# encoder_isolator.net
KiCad netlist of a schematic drawn in EAGLE
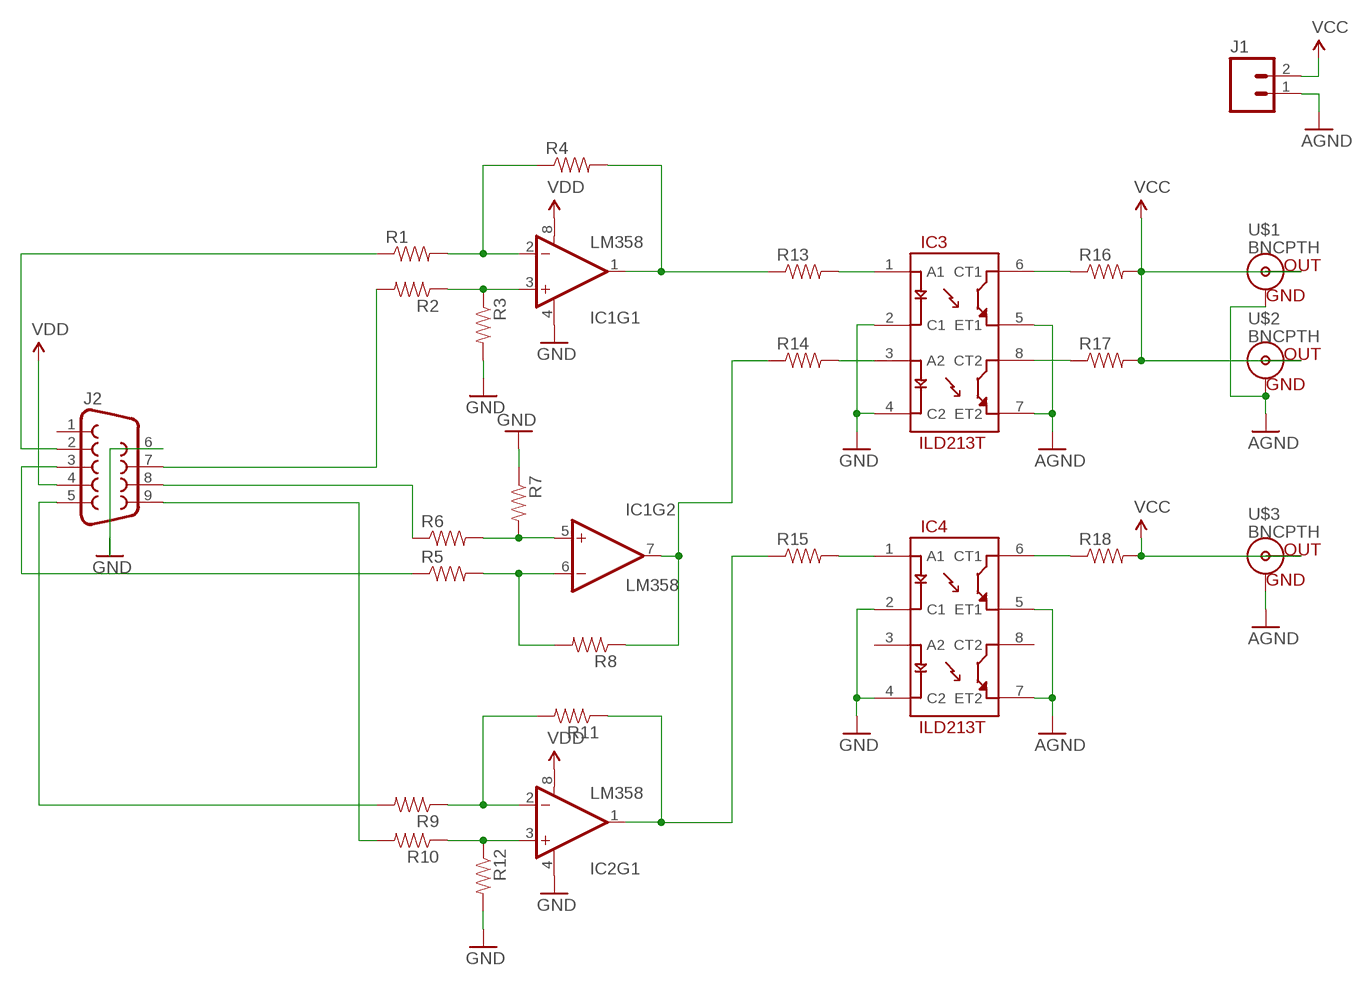
[diagram p0: schematic, sheet 1]

(export (version "E")
  (design (tool "Eeschema 10.0.6"))
  (components
    (comp (ref "IC1")
      (value "LM358")
      (footprint "eagle-import:DIP08")
      (libsource (lib "eagle-import") (part "LM358"))
    )
    (comp (ref "IC2")
      (value "LM358")
      (footprint "eagle-import:DIP08")
      (libsource (lib "eagle-import") (part "LM358"))
    )
    (comp (ref "IC3")
      (value "ILD213T")
      (footprint "eagle-import:SO08")
      (libsource (lib "eagle-import") (part "ILD213T"))
    )
    (comp (ref "IC4")
      (value "ILD213T")
      (footprint "eagle-import:SO08")
      (libsource (lib "eagle-import") (part "ILD213T"))
    )
    (comp (ref "J1")
      (value "M02POLAR")
      (footprint "eagle-import:MOLEX-1X2")
      (libsource (lib "eagle-import") (part "M02POLAR"))
    )
    (comp (ref "J2")
      (value "DB9FEMALE")
      (footprint "eagle-import:DB9")
      (libsource (lib "eagle-import") (part "DB9FEMALE"))
    )
    (comp (ref "R1")
      (value "RESISTORPTH-1/4W")
      (footprint "eagle-import:AXIAL-0.4")
      (libsource (lib "eagle-import") (part "RESISTORPTH-1/4W"))
    )
    (comp (ref "R2")
      (value "RESISTORPTH-1/4W")
      (footprint "eagle-import:AXIAL-0.4")
      (libsource (lib "eagle-import") (part "RESISTORPTH-1/4W"))
    )
    (comp (ref "R3")
      (value "RESISTORPTH-1/4W")
      (footprint "eagle-import:AXIAL-0.4")
      (libsource (lib "eagle-import") (part "RESISTORPTH-1/4W"))
    )
    (comp (ref "R4")
      (value "RESISTORPTH-1/4W")
      (footprint "eagle-import:AXIAL-0.4")
      (libsource (lib "eagle-import") (part "RESISTORPTH-1/4W"))
    )
    (comp (ref "R5")
      (value "RESISTORPTH-1/4W")
      (footprint "eagle-import:AXIAL-0.4")
      (libsource (lib "eagle-import") (part "RESISTORPTH-1/4W"))
    )
    (comp (ref "R6")
      (value "RESISTORPTH-1/4W")
      (footprint "eagle-import:AXIAL-0.4")
      (libsource (lib "eagle-import") (part "RESISTORPTH-1/4W"))
    )
    (comp (ref "R7")
      (value "RESISTORPTH-1/4W")
      (footprint "eagle-import:AXIAL-0.4")
      (libsource (lib "eagle-import") (part "RESISTORPTH-1/4W"))
    )
    (comp (ref "R8")
      (value "RESISTORPTH-1/4W")
      (footprint "eagle-import:AXIAL-0.4")
      (libsource (lib "eagle-import") (part "RESISTORPTH-1/4W"))
    )
    (comp (ref "R9")
      (value "RESISTORPTH-1/4W")
      (footprint "eagle-import:AXIAL-0.4")
      (libsource (lib "eagle-import") (part "RESISTORPTH-1/4W"))
    )
    (comp (ref "R10")
      (value "RESISTORPTH-1/4W")
      (footprint "eagle-import:AXIAL-0.4")
      (libsource (lib "eagle-import") (part "RESISTORPTH-1/4W"))
    )
    (comp (ref "R11")
      (value "RESISTORPTH-1/4W")
      (footprint "eagle-import:AXIAL-0.4")
      (libsource (lib "eagle-import") (part "RESISTORPTH-1/4W"))
    )
    (comp (ref "R12")
      (value "RESISTORPTH-1/4W")
      (footprint "eagle-import:AXIAL-0.4")
      (libsource (lib "eagle-import") (part "RESISTORPTH-1/4W"))
    )
    (comp (ref "R13")
      (value "RESISTORPTH-1/4W")
      (footprint "eagle-import:AXIAL-0.4")
      (libsource (lib "eagle-import") (part "RESISTORPTH-1/4W"))
    )
    (comp (ref "R14")
      (value "RESISTORPTH-1/4W")
      (footprint "eagle-import:AXIAL-0.4")
      (libsource (lib "eagle-import") (part "RESISTORPTH-1/4W"))
    )
    (comp (ref "R15")
      (value "RESISTORPTH-1/4W")
      (footprint "eagle-import:AXIAL-0.4")
      (libsource (lib "eagle-import") (part "RESISTORPTH-1/4W"))
    )
    (comp (ref "R16")
      (value "RESISTORPTH-1/4W")
      (footprint "eagle-import:AXIAL-0.4")
      (libsource (lib "eagle-import") (part "RESISTORPTH-1/4W"))
    )
    (comp (ref "R17")
      (value "RESISTORPTH-1/4W")
      (footprint "eagle-import:AXIAL-0.4")
      (libsource (lib "eagle-import") (part "RESISTORPTH-1/4W"))
    )
    (comp (ref "R18")
      (value "RESISTORPTH-1/4W")
      (footprint "eagle-import:AXIAL-0.4")
      (libsource (lib "eagle-import") (part "RESISTORPTH-1/4W"))
    )
    (comp (ref "U$1")
      (value "BNCPTH")
      (footprint "eagle-import:BNC")
      (libsource (lib "eagle-import") (part "BNCPTH"))
    )
    (comp (ref "U$2")
      (value "BNCPTH")
      (footprint "eagle-import:BNC")
      (libsource (lib "eagle-import") (part "BNCPTH"))
    )
    (comp (ref "U$3")
      (value "BNCPTH")
      (footprint "eagle-import:BNC")
      (libsource (lib "eagle-import") (part "BNCPTH"))
    )
  )
  (nets
    (net (code "1") (name "AGND") (class "Default")
      (node (ref "IC3") (pin "5") (pinfunction "ET1_5") (pintype "bidirectional"))
      (node (ref "IC3") (pin "7") (pinfunction "ET2_7") (pintype "bidirectional"))
      (node (ref "IC4") (pin "5") (pinfunction "ET1_5") (pintype "bidirectional"))
      (node (ref "IC4") (pin "7") (pinfunction "ET2_7") (pintype "bidirectional"))
      (node (ref "J1") (pin "1") (pinfunction "1_1") (pintype "passive"))
      (node (ref "U$1") (pin "GND") (pinfunction "GND_GND") (pintype "bidirectional"))
      (node (ref "U$2") (pin "GND") (pinfunction "GND_GND") (pintype "bidirectional"))
      (node (ref "U$3") (pin "GND") (pinfunction "GND_GND") (pintype "bidirectional"))
    )
    (net (code "2") (name "GND") (class "Default")
      (node (ref "IC1") (pin "4") (pinfunction "V-_4") (pintype "power_in"))
      (node (ref "IC2") (pin "4") (pinfunction "V-_4") (pintype "power_in"))
      (node (ref "IC3") (pin "2") (pinfunction "C1_2") (pintype "bidirectional"))
      (node (ref "IC3") (pin "4") (pinfunction "C2_4") (pintype "bidirectional"))
      (node (ref "IC4") (pin "2") (pinfunction "C1_2") (pintype "bidirectional"))
      (node (ref "IC4") (pin "4") (pinfunction "C2_4") (pintype "bidirectional"))
      (node (ref "J2") (pin "6") (pinfunction "6_6") (pintype "passive"))
      (node (ref "R12") (pin "P$2") (pinfunction "2_P$2") (pintype "passive"))
      (node (ref "R3") (pin "P$2") (pinfunction "2_P$2") (pintype "passive"))
      (node (ref "R7") (pin "P$1") (pinfunction "1_P$1") (pintype "passive"))
    )
    (net (code "3") (name "Net-(IC1A-+IN)") (class "Default")
      (node (ref "IC1") (pin "3") (pinfunction "+IN_3") (pintype "input"))
      (node (ref "R2") (pin "P$1") (pinfunction "1_P$1") (pintype "passive"))
      (node (ref "R3") (pin "P$1") (pinfunction "1_P$1") (pintype "passive"))
    )
    (net (code "4") (name "Net-(IC1A--IN)") (class "Default")
      (node (ref "IC1") (pin "2") (pinfunction "-IN_2") (pintype "input"))
      (node (ref "R1") (pin "P$2") (pinfunction "2_P$2") (pintype "passive"))
      (node (ref "R4") (pin "P$1") (pinfunction "1_P$1") (pintype "passive"))
    )
    (net (code "5") (name "Net-(IC1A-OUT)") (class "Default")
      (node (ref "IC1") (pin "1") (pinfunction "OUT_1") (pintype "output"))
      (node (ref "R13") (pin "P$1") (pinfunction "1_P$1") (pintype "passive"))
      (node (ref "R4") (pin "P$2") (pinfunction "2_P$2") (pintype "passive"))
    )
    (net (code "6") (name "Net-(IC1B-+IN)") (class "Default")
      (node (ref "IC1") (pin "5") (pinfunction "+IN_5") (pintype "input"))
      (node (ref "R6") (pin "P$2") (pinfunction "2_P$2") (pintype "passive"))
      (node (ref "R7") (pin "P$2") (pinfunction "2_P$2") (pintype "passive"))
    )
    (net (code "7") (name "Net-(IC1B--IN)") (class "Default")
      (node (ref "IC1") (pin "6") (pinfunction "-IN_6") (pintype "input"))
      (node (ref "R5") (pin "P$2") (pinfunction "2_P$2") (pintype "passive"))
      (node (ref "R8") (pin "P$2") (pinfunction "2_P$2") (pintype "passive"))
    )
    (net (code "8") (name "Net-(IC1B-OUT)") (class "Default")
      (node (ref "IC1") (pin "7") (pinfunction "OUT_7") (pintype "output"))
      (node (ref "R14") (pin "P$1") (pinfunction "1_P$1") (pintype "passive"))
      (node (ref "R8") (pin "P$1") (pinfunction "1_P$1") (pintype "passive"))
    )
    (net (code "9") (name "Net-(IC2A-+IN)") (class "Default")
      (node (ref "IC2") (pin "3") (pinfunction "+IN_3") (pintype "input"))
      (node (ref "R10") (pin "P$1") (pinfunction "1_P$1") (pintype "passive"))
      (node (ref "R12") (pin "P$1") (pinfunction "1_P$1") (pintype "passive"))
    )
    (net (code "10") (name "Net-(IC2A--IN)") (class "Default")
      (node (ref "IC2") (pin "2") (pinfunction "-IN_2") (pintype "input"))
      (node (ref "R11") (pin "P$2") (pinfunction "2_P$2") (pintype "passive"))
      (node (ref "R9") (pin "P$1") (pinfunction "1_P$1") (pintype "passive"))
    )
    (net (code "11") (name "Net-(IC2A-OUT)") (class "Default")
      (node (ref "IC2") (pin "1") (pinfunction "OUT_1") (pintype "output"))
      (node (ref "R11") (pin "P$1") (pinfunction "1_P$1") (pintype "passive"))
      (node (ref "R15") (pin "P$1") (pinfunction "1_P$1") (pintype "passive"))
    )
    (net (code "12") (name "Net-(IC3-A1)") (class "Default")
      (node (ref "IC3") (pin "1") (pinfunction "A1_1") (pintype "bidirectional"))
      (node (ref "R13") (pin "P$2") (pinfunction "2_P$2") (pintype "passive"))
    )
    (net (code "13") (name "Net-(IC3-A2)") (class "Default")
      (node (ref "IC3") (pin "3") (pinfunction "A2_3") (pintype "bidirectional"))
      (node (ref "R14") (pin "P$2") (pinfunction "2_P$2") (pintype "passive"))
    )
    (net (code "14") (name "Net-(IC3-CT1)") (class "Default")
      (node (ref "IC3") (pin "6") (pinfunction "CT1_6") (pintype "bidirectional"))
      (node (ref "R16") (pin "P$1") (pinfunction "1_P$1") (pintype "passive"))
    )
    (net (code "15") (name "Net-(IC3-CT2)") (class "Default")
      (node (ref "IC3") (pin "8") (pinfunction "CT2_8") (pintype "bidirectional"))
      (node (ref "R17") (pin "P$1") (pinfunction "1_P$1") (pintype "passive"))
    )
    (net (code "16") (name "Net-(IC4-A1)") (class "Default")
      (node (ref "IC4") (pin "1") (pinfunction "A1_1") (pintype "bidirectional"))
      (node (ref "R15") (pin "P$2") (pinfunction "2_P$2") (pintype "passive"))
    )
    (net (code "17") (name "Net-(IC4-CT1)") (class "Default")
      (node (ref "IC4") (pin "6") (pinfunction "CT1_6") (pintype "bidirectional"))
      (node (ref "R18") (pin "P$1") (pinfunction "1_P$1") (pintype "passive"))
    )
    (net (code "18") (name "Net-(R1-1)") (class "Default")
      (node (ref "J2") (pin "2") (pinfunction "2_2") (pintype "passive"))
      (node (ref "R1") (pin "P$1") (pinfunction "1_P$1") (pintype "passive"))
    )
    (net (code "19") (name "Net-(R2-2)") (class "Default")
      (node (ref "J2") (pin "7") (pinfunction "7_7") (pintype "passive"))
      (node (ref "R2") (pin "P$2") (pinfunction "2_P$2") (pintype "passive"))
    )
    (net (code "20") (name "Net-(R5-1)") (class "Default")
      (node (ref "J2") (pin "3") (pinfunction "3_3") (pintype "passive"))
      (node (ref "R5") (pin "P$1") (pinfunction "1_P$1") (pintype "passive"))
    )
    (net (code "21") (name "Net-(R6-1)") (class "Default")
      (node (ref "J2") (pin "8") (pinfunction "8_8") (pintype "passive"))
      (node (ref "R6") (pin "P$1") (pinfunction "1_P$1") (pintype "passive"))
    )
    (net (code "22") (name "Net-(R9-2)") (class "Default")
      (node (ref "J2") (pin "5") (pinfunction "5_5") (pintype "passive"))
      (node (ref "R9") (pin "P$2") (pinfunction "2_P$2") (pintype "passive"))
    )
    (net (code "23") (name "Net-(R10-2)") (class "Default")
      (node (ref "J2") (pin "9") (pinfunction "9_9") (pintype "passive"))
      (node (ref "R10") (pin "P$2") (pinfunction "2_P$2") (pintype "passive"))
    )
    (net (code "24") (name "VCC") (class "Default")
      (node (ref "J1") (pin "2") (pinfunction "2_2") (pintype "passive"))
      (node (ref "R16") (pin "P$2") (pinfunction "2_P$2") (pintype "passive"))
      (node (ref "R17") (pin "P$2") (pinfunction "2_P$2") (pintype "passive"))
      (node (ref "R18") (pin "P$2") (pinfunction "2_P$2") (pintype "passive"))
      (node (ref "U$1") (pin "S") (pinfunction "OUT_S") (pintype "bidirectional"))
      (node (ref "U$2") (pin "S") (pinfunction "OUT_S") (pintype "bidirectional"))
      (node (ref "U$3") (pin "S") (pinfunction "OUT_S") (pintype "bidirectional"))
    )
    (net (code "25") (name "VDD") (class "Default")
      (node (ref "IC1") (pin "8") (pinfunction "V+_8") (pintype "power_in"))
      (node (ref "IC2") (pin "8") (pinfunction "V+_8") (pintype "power_in"))
      (node (ref "J2") (pin "4") (pinfunction "4_4") (pintype "passive"))
    )
    (net (code "26") (name "unconnected-(IC4-A2-Pad3)") (class "Default")
      (node (ref "IC4") (pin "3") (pinfunction "A2_3") (pintype "bidirectional"))
    )
    (net (code "27") (name "unconnected-(IC4-CT2-Pad8)") (class "Default")
      (node (ref "IC4") (pin "8") (pinfunction "CT2_8") (pintype "bidirectional"))
    )
    (net (code "28") (name "unconnected-(J2-Pad1)") (class "Default")
      (node (ref "J2") (pin "1") (pinfunction "1_1") (pintype "passive"))
    )
  )
)
